# MBO.net
KiCad netlist of a schematic drawn in EAGLE
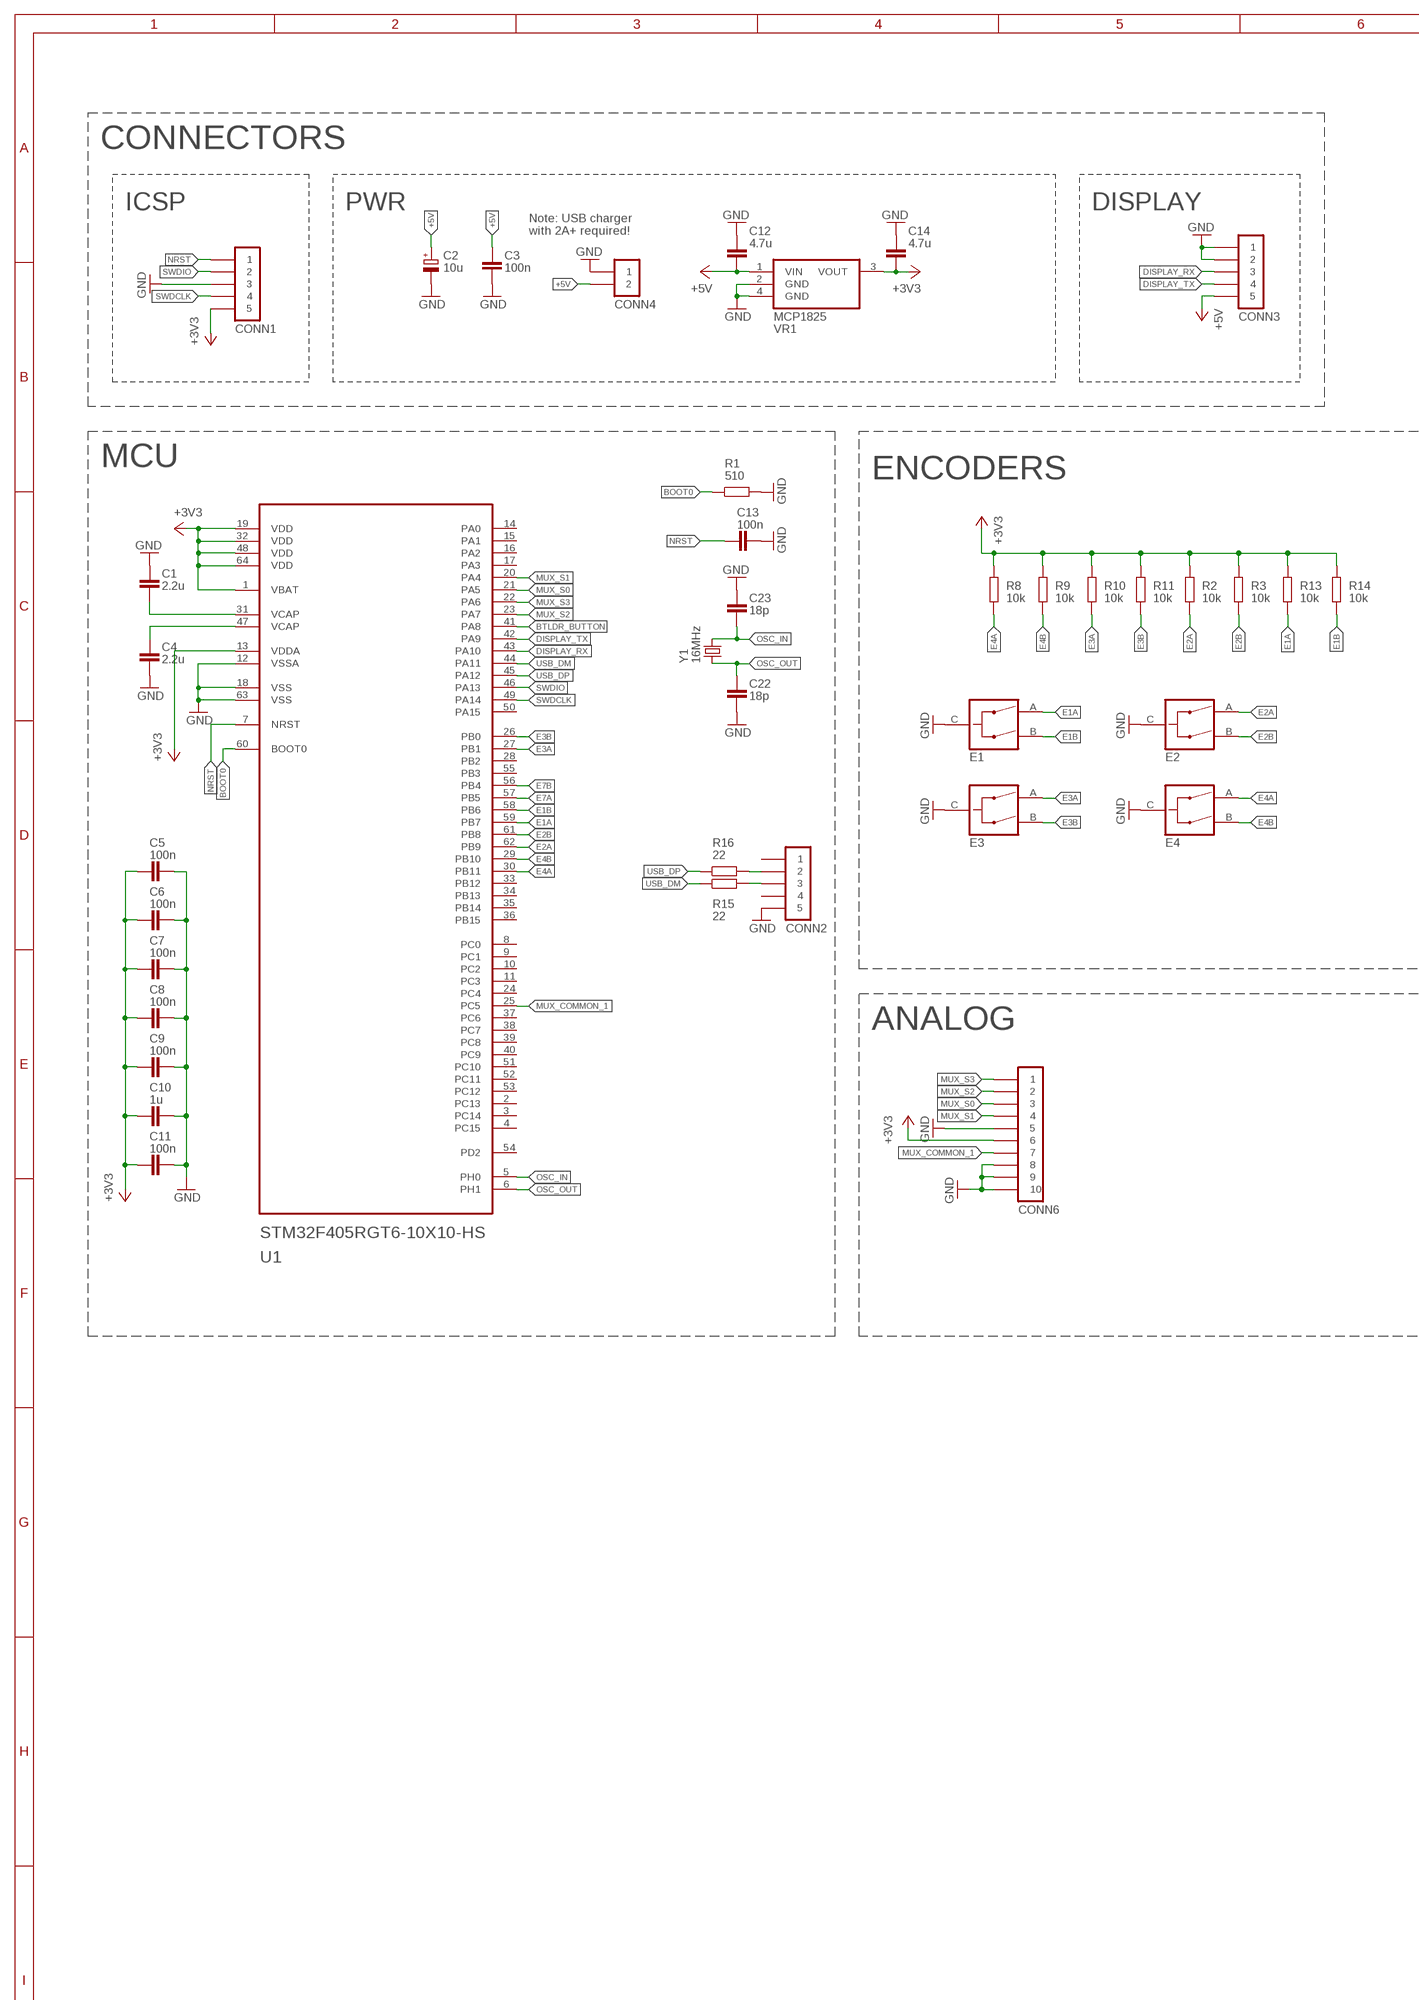
[diagram p0: schematic, sheet 1, part 1 of 2]
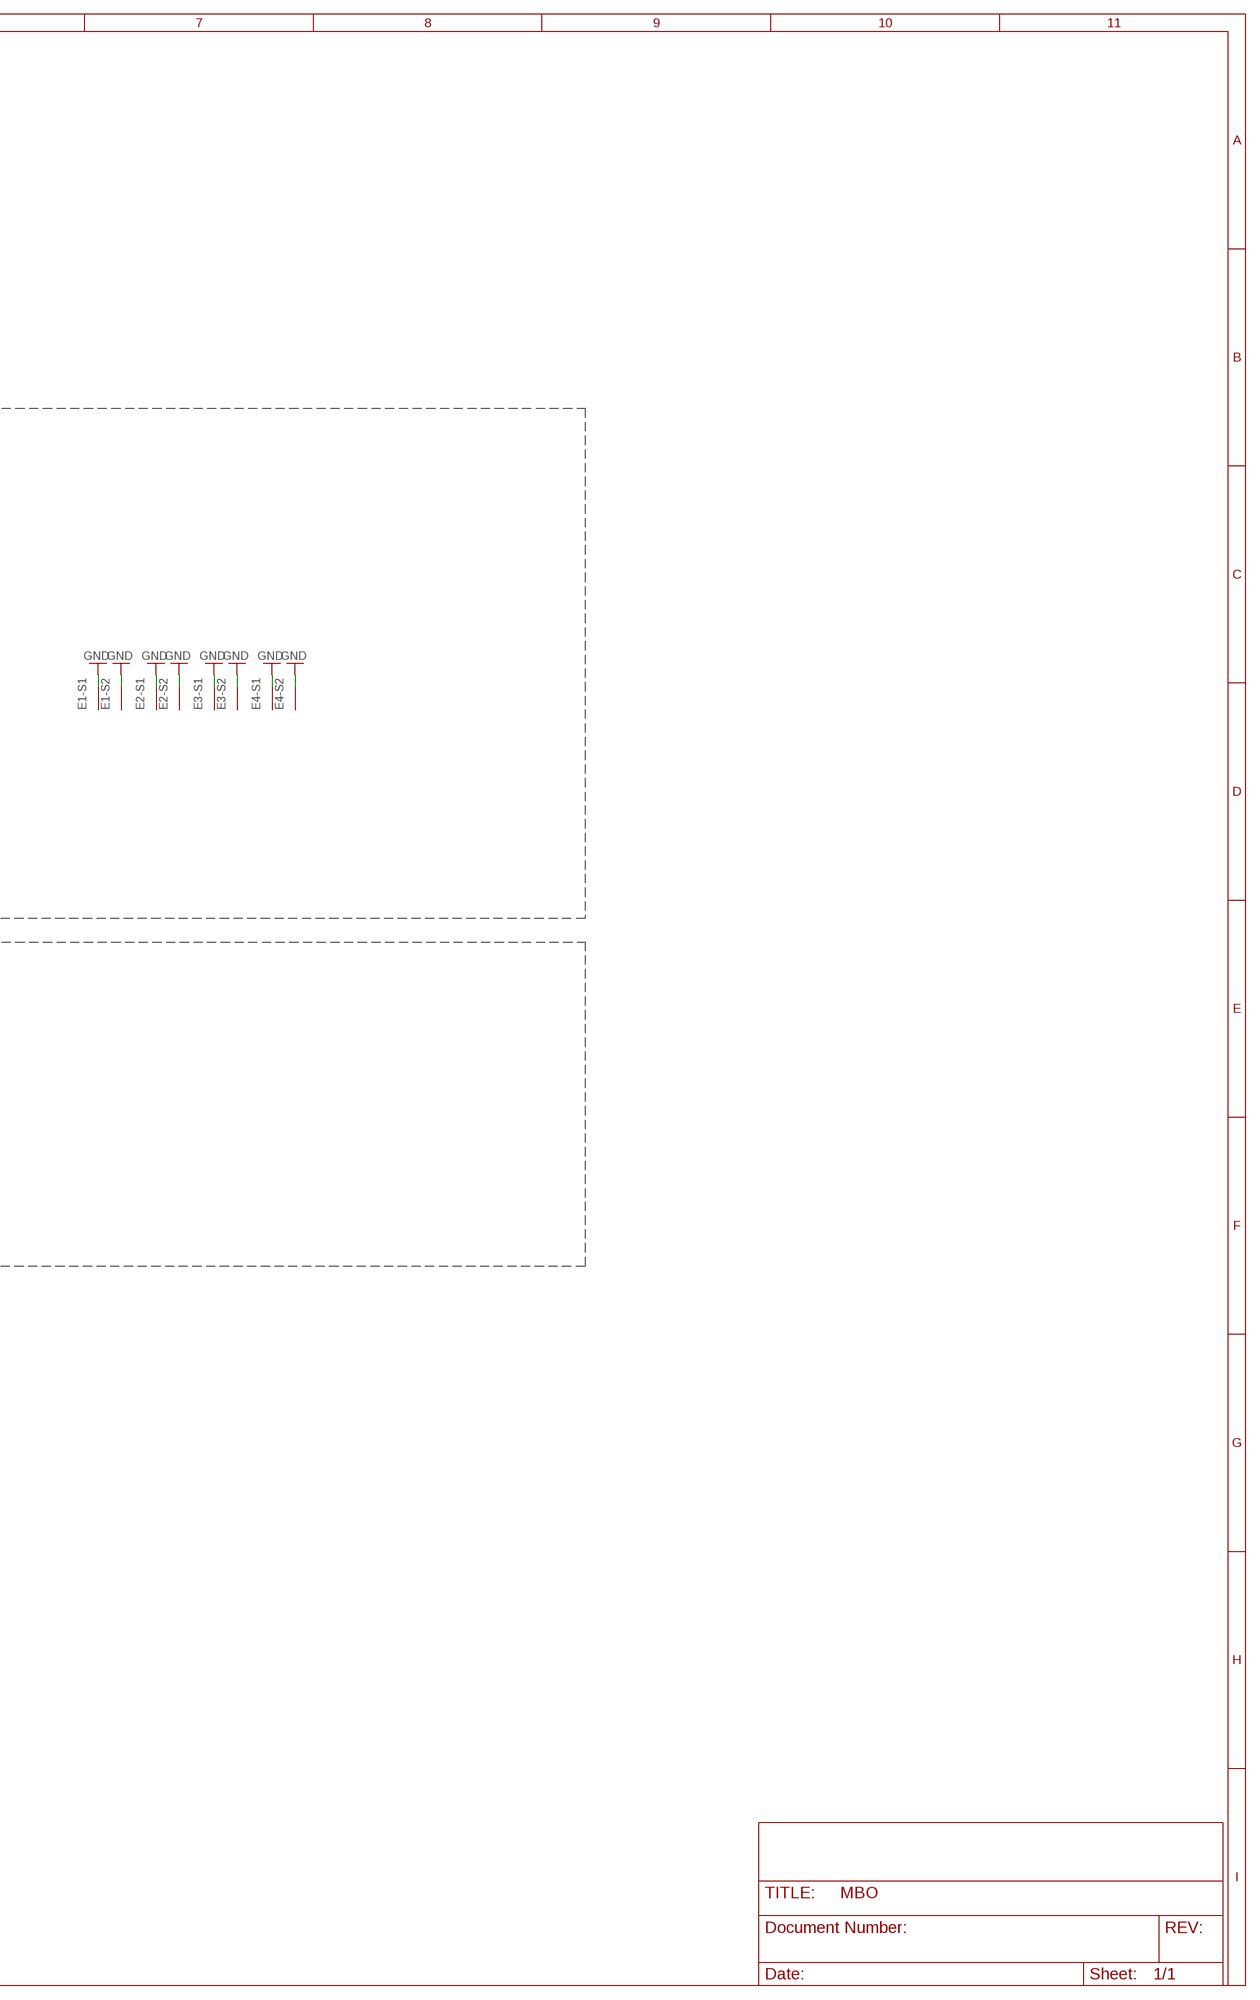
[diagram p1: schematic, sheet 1, part 2 of 2]

(export (version "E")
  (design (tool "Eeschema 10.0.6"))
  (components
    (comp (ref "C1")
      (value "2.2u")
      (footprint "eagle-import:C0805")
      (libsource (lib "eagle-import") (part "CAPACITOR-0805"))
    )
    (comp (ref "C2")
      (value "10u")
      (footprint "eagle-import:C-TH-E-0401")
      (libsource (lib "eagle-import") (part "ELECTROLYTIC_CAPACITOR-C-TH-E-0401"))
    )
    (comp (ref "C3")
      (value "100n")
      (footprint "eagle-import:C0805")
      (libsource (lib "eagle-import") (part "CAPACITOR-0805"))
    )
    (comp (ref "C4")
      (value "2.2u")
      (footprint "eagle-import:C0805")
      (libsource (lib "eagle-import") (part "CAPACITOR-0805"))
    )
    (comp (ref "C5")
      (value "100n")
      (footprint "eagle-import:C0805")
      (libsource (lib "eagle-import") (part "CAPACITOR-0805"))
    )
    (comp (ref "C6")
      (value "100n")
      (footprint "eagle-import:C0805")
      (libsource (lib "eagle-import") (part "CAPACITOR-0805"))
    )
    (comp (ref "C7")
      (value "100n")
      (footprint "eagle-import:C0805")
      (libsource (lib "eagle-import") (part "CAPACITOR-0805"))
    )
    (comp (ref "C8")
      (value "100n")
      (footprint "eagle-import:C0805")
      (libsource (lib "eagle-import") (part "CAPACITOR-0805"))
    )
    (comp (ref "C9")
      (value "100n")
      (footprint "eagle-import:C0805")
      (libsource (lib "eagle-import") (part "CAPACITOR-0805"))
    )
    (comp (ref "C10")
      (value "1u")
      (footprint "eagle-import:C0805")
      (libsource (lib "eagle-import") (part "CAPACITOR-0805"))
    )
    (comp (ref "C11")
      (value "100n")
      (footprint "eagle-import:C0805")
      (libsource (lib "eagle-import") (part "CAPACITOR-0805"))
    )
    (comp (ref "C12")
      (value "4.7u")
      (footprint "eagle-import:C0805")
      (libsource (lib "eagle-import") (part "CAPACITOR-0805"))
    )
    (comp (ref "C13")
      (value "100n")
      (footprint "eagle-import:C0805")
      (libsource (lib "eagle-import") (part "CAPACITOR-0805"))
    )
    (comp (ref "C14")
      (value "4.7u")
      (footprint "eagle-import:C0805")
      (libsource (lib "eagle-import") (part "CAPACITOR-0805"))
    )
    (comp (ref "C22")
      (value "18p")
      (footprint "eagle-import:C0805")
      (libsource (lib "eagle-import") (part "CAPACITOR-0805"))
    )
    (comp (ref "C23")
      (value "18p")
      (footprint "eagle-import:C0805")
      (libsource (lib "eagle-import") (part "CAPACITOR-0805"))
    )
    (comp (ref "CONN1")
      (value "PINHD-1X05-TH-2.54MM")
      (footprint "eagle-import:1X05-2.54")
      (libsource (lib "eagle-import") (part "PINHD-1X05-TH-2.54MM"))
    )
    (comp (ref "CONN2")
      (value "PINHD-1X05-JST-XH-H")
      (footprint "eagle-import:JST-XH-05P-H")
      (libsource (lib "eagle-import") (part "PINHD-1X05-JST-XH-H"))
    )
    (comp (ref "CONN3")
      (value "PINHD-1X05-JST-XH-H")
      (footprint "eagle-import:JST-XH-05P-H")
      (libsource (lib "eagle-import") (part "PINHD-1X05-JST-XH-H"))
    )
    (comp (ref "CONN4")
      (value "PINHD-1X02-JST-XH-H")
      (footprint "eagle-import:JST-XH-02P-H")
      (libsource (lib "eagle-import") (part "PINHD-1X02-JST-XH-H"))
    )
    (comp (ref "CONN6")
      (value "PINHD-1X10-FFC-1MM-Z")
      (footprint "eagle-import:MOLEX-52271-1079")
      (fields (field (name "MANUFACTURER") "Molex") (field (name "MPN") "52271-1079"))
      (libsource (lib "eagle-import") (part "PINHD-1X10-FFC-1MM-Z"))
    )
    (comp (ref "E1")
      (value "ALPS-EC12E24404AX")
      (footprint "eagle-import:EC12E-1")
      (libsource (lib "eagle-import") (part "ALPS-EC12E24404AX"))
    )
    (comp (ref "E2")
      (value "ALPS-EC12E24404AX")
      (footprint "eagle-import:EC12E-1")
      (libsource (lib "eagle-import") (part "ALPS-EC12E24404AX"))
    )
    (comp (ref "E3")
      (value "ALPS-EC12E24404AX")
      (footprint "eagle-import:EC12E-1")
      (libsource (lib "eagle-import") (part "ALPS-EC12E24404AX"))
    )
    (comp (ref "E4")
      (value "ALPS-EC12E24404AX")
      (footprint "eagle-import:EC12E-1")
      (libsource (lib "eagle-import") (part "ALPS-EC12E24404AX"))
    )
    (comp (ref "R1")
      (value "510")
      (footprint "eagle-import:R0805")
      (libsource (lib "eagle-import") (part "RESISTOR-0805"))
    )
    (comp (ref "R2")
      (value "10k")
      (footprint "eagle-import:R0805")
      (libsource (lib "eagle-import") (part "RESISTOR-0805"))
    )
    (comp (ref "R3")
      (value "10k")
      (footprint "eagle-import:R0805")
      (libsource (lib "eagle-import") (part "RESISTOR-0805"))
    )
    (comp (ref "R8")
      (value "10k")
      (footprint "eagle-import:R0805")
      (libsource (lib "eagle-import") (part "RESISTOR-0805"))
    )
    (comp (ref "R9")
      (value "10k")
      (footprint "eagle-import:R0805")
      (libsource (lib "eagle-import") (part "RESISTOR-0805"))
    )
    (comp (ref "R10")
      (value "10k")
      (footprint "eagle-import:R0805")
      (libsource (lib "eagle-import") (part "RESISTOR-0805"))
    )
    (comp (ref "R11")
      (value "10k")
      (footprint "eagle-import:R0805")
      (libsource (lib "eagle-import") (part "RESISTOR-0805"))
    )
    (comp (ref "R13")
      (value "10k")
      (footprint "eagle-import:R0805")
      (libsource (lib "eagle-import") (part "RESISTOR-0805"))
    )
    (comp (ref "R14")
      (value "10k")
      (footprint "eagle-import:R0805")
      (libsource (lib "eagle-import") (part "RESISTOR-0805"))
    )
    (comp (ref "R15")
      (value "22")
      (footprint "eagle-import:R0805")
      (libsource (lib "eagle-import") (part "RESISTOR-0805"))
    )
    (comp (ref "R16")
      (value "22")
      (footprint "eagle-import:R0805")
      (libsource (lib "eagle-import") (part "RESISTOR-0805"))
    )
    (comp (ref "U1")
      (value "STM32F405RGT6-10X10-HS")
      (footprint "eagle-import:TQFP-64-10X10-HS")
      (libsource (lib "eagle-import") (part "STM32F405RGT6-10X10-HS"))
    )
    (comp (ref "VR1")
      (value "MCP1825")
      (footprint "eagle-import:SOT223")
      (fields (field (name "MANUFACTURER") "Microchip") (field (name "MPN") "MCP1825S-3302E/DB"))
      (libsource (lib "eagle-import") (part "MCP1825"))
    )
    (comp (ref "Y1")
      (value "16MHz")
      (footprint "eagle-import:HC49US")
      (fields (field (name "MANUFACTURER") "TXC") (field (name "MPN") "9B-16.000MEEJ-B"))
      (libsource (lib "eagle-import") (part "CRYSTAL-HC49"))
    )
  )
  (nets
    (net (code "1") (name "+3V3") (class "Default")
      (node (ref "C10") (pin "1") (pinfunction "1_1") (pintype "passive"))
      (node (ref "C11") (pin "1") (pinfunction "1_1") (pintype "passive"))
      (node (ref "C14") (pin "1") (pinfunction "1_1") (pintype "passive"))
      (node (ref "C5") (pin "1") (pinfunction "1_1") (pintype "passive"))
      (node (ref "C6") (pin "1") (pinfunction "1_1") (pintype "passive"))
      (node (ref "C7") (pin "1") (pinfunction "1_1") (pintype "passive"))
      (node (ref "C8") (pin "1") (pinfunction "1_1") (pintype "passive"))
      (node (ref "C9") (pin "1") (pinfunction "1_1") (pintype "passive"))
      (node (ref "CONN1") (pin "5") (pinfunction "5_5") (pintype "passive"))
      (node (ref "CONN6") (pin "6") (pinfunction "6_6") (pintype "passive"))
      (node (ref "R10") (pin "2") (pinfunction "2_2") (pintype "passive"))
      (node (ref "R11") (pin "2") (pinfunction "2_2") (pintype "passive"))
      (node (ref "R13") (pin "2") (pinfunction "2_2") (pintype "passive"))
      (node (ref "R14") (pin "2") (pinfunction "2_2") (pintype "passive"))
      (node (ref "R2") (pin "2") (pinfunction "2_2") (pintype "passive"))
      (node (ref "R3") (pin "2") (pinfunction "2_2") (pintype "passive"))
      (node (ref "R8") (pin "2") (pinfunction "2_2") (pintype "passive"))
      (node (ref "R9") (pin "2") (pinfunction "2_2") (pintype "passive"))
      (node (ref "U1") (pin "1") (pinfunction "VBAT_1") (pintype "bidirectional"))
      (node (ref "U1") (pin "13") (pinfunction "VDDA_13") (pintype "bidirectional"))
      (node (ref "U1") (pin "19") (pinfunction "VDD_19") (pintype "bidirectional"))
      (node (ref "U1") (pin "32") (pinfunction "VDD_32") (pintype "bidirectional"))
      (node (ref "U1") (pin "48") (pinfunction "VDD_48") (pintype "bidirectional"))
      (node (ref "U1") (pin "64") (pinfunction "VDD_64") (pintype "bidirectional"))
      (node (ref "VR1") (pin "3") (pinfunction "VOUT_3") (pintype "passive"))
    )
    (net (code "2") (name "+5V") (class "Default")
      (node (ref "C12") (pin "1") (pinfunction "1_1") (pintype "passive"))
      (node (ref "C2") (pin "+") (pinfunction "+_+") (pintype "passive"))
      (node (ref "C3") (pin "1") (pinfunction "1_1") (pintype "passive"))
      (node (ref "CONN3") (pin "5") (pinfunction "5_5") (pintype "passive"))
      (node (ref "CONN4") (pin "2") (pinfunction "2_2") (pintype "passive"))
      (node (ref "VR1") (pin "1") (pinfunction "VIN_1") (pintype "passive"))
    )
    (net (code "3") (name "BOOT0") (class "Default")
      (node (ref "R1") (pin "1") (pinfunction "1_1") (pintype "passive"))
      (node (ref "U1") (pin "60") (pinfunction "BOOT0_60") (pintype "bidirectional"))
    )
    (net (code "4") (name "BTLDR_BUTTON") (class "Default")
      (node (ref "U1") (pin "41") (pinfunction "PA8_41") (pintype "bidirectional"))
    )
    (net (code "5") (name "DISPLAY_RX") (class "Default")
      (node (ref "CONN3") (pin "3") (pinfunction "3_3") (pintype "passive"))
      (node (ref "U1") (pin "43") (pinfunction "PA10_43") (pintype "bidirectional"))
    )
    (net (code "6") (name "DISPLAY_TX") (class "Default")
      (node (ref "CONN3") (pin "4") (pinfunction "4_4") (pintype "passive"))
      (node (ref "U1") (pin "42") (pinfunction "PA9_42") (pintype "bidirectional"))
    )
    (net (code "7") (name "E1A") (class "Default")
      (node (ref "E1") (pin "A") (pinfunction "A_A") (pintype "output"))
      (node (ref "R13") (pin "1") (pinfunction "1_1") (pintype "passive"))
      (node (ref "U1") (pin "59") (pinfunction "PB7_59") (pintype "bidirectional"))
    )
    (net (code "8") (name "E1B") (class "Default")
      (node (ref "E1") (pin "B") (pinfunction "B_B") (pintype "output"))
      (node (ref "R14") (pin "1") (pinfunction "1_1") (pintype "passive"))
      (node (ref "U1") (pin "58") (pinfunction "PB6_58") (pintype "bidirectional"))
    )
    (net (code "9") (name "E2A") (class "Default")
      (node (ref "E2") (pin "A") (pinfunction "A_A") (pintype "output"))
      (node (ref "R2") (pin "1") (pinfunction "1_1") (pintype "passive"))
      (node (ref "U1") (pin "62") (pinfunction "PB9_62") (pintype "bidirectional"))
    )
    (net (code "10") (name "E2B") (class "Default")
      (node (ref "E2") (pin "B") (pinfunction "B_B") (pintype "output"))
      (node (ref "R3") (pin "1") (pinfunction "1_1") (pintype "passive"))
      (node (ref "U1") (pin "61") (pinfunction "PB8_61") (pintype "bidirectional"))
    )
    (net (code "11") (name "E3A") (class "Default")
      (node (ref "E3") (pin "A") (pinfunction "A_A") (pintype "output"))
      (node (ref "R10") (pin "1") (pinfunction "1_1") (pintype "passive"))
      (node (ref "U1") (pin "27") (pinfunction "PB1_27") (pintype "bidirectional"))
    )
    (net (code "12") (name "E3B") (class "Default")
      (node (ref "E3") (pin "B") (pinfunction "B_B") (pintype "output"))
      (node (ref "R11") (pin "1") (pinfunction "1_1") (pintype "passive"))
      (node (ref "U1") (pin "26") (pinfunction "PB0_26") (pintype "bidirectional"))
    )
    (net (code "13") (name "E4A") (class "Default")
      (node (ref "E4") (pin "A") (pinfunction "A_A") (pintype "output"))
      (node (ref "R8") (pin "1") (pinfunction "1_1") (pintype "passive"))
      (node (ref "U1") (pin "30") (pinfunction "PB11_30") (pintype "bidirectional"))
    )
    (net (code "14") (name "E4B") (class "Default")
      (node (ref "E4") (pin "B") (pinfunction "B_B") (pintype "output"))
      (node (ref "R9") (pin "1") (pinfunction "1_1") (pintype "passive"))
      (node (ref "U1") (pin "29") (pinfunction "PB10_29") (pintype "bidirectional"))
    )
    (net (code "15") (name "E7A") (class "Default")
      (node (ref "U1") (pin "57") (pinfunction "PB5_57") (pintype "bidirectional"))
    )
    (net (code "16") (name "E7B") (class "Default")
      (node (ref "U1") (pin "56") (pinfunction "PB4_56") (pintype "bidirectional"))
    )
    (net (code "17") (name "GND") (class "Default")
      (node (ref "C1") (pin "1") (pinfunction "1_1") (pintype "passive"))
      (node (ref "C10") (pin "2") (pinfunction "2_2") (pintype "passive"))
      (node (ref "C11") (pin "2") (pinfunction "2_2") (pintype "passive"))
      (node (ref "C12") (pin "2") (pinfunction "2_2") (pintype "passive"))
      (node (ref "C13") (pin "2") (pinfunction "2_2") (pintype "passive"))
      (node (ref "C14") (pin "2") (pinfunction "2_2") (pintype "passive"))
      (node (ref "C2") (pin "-") (pinfunction "-_-") (pintype "passive"))
      (node (ref "C22") (pin "2") (pinfunction "2_2") (pintype "passive"))
      (node (ref "C23") (pin "1") (pinfunction "1_1") (pintype "passive"))
      (node (ref "C3") (pin "2") (pinfunction "2_2") (pintype "passive"))
      (node (ref "C4") (pin "2") (pinfunction "2_2") (pintype "passive"))
      (node (ref "C5") (pin "2") (pinfunction "2_2") (pintype "passive"))
      (node (ref "C6") (pin "2") (pinfunction "2_2") (pintype "passive"))
      (node (ref "C7") (pin "2") (pinfunction "2_2") (pintype "passive"))
      (node (ref "C8") (pin "2") (pinfunction "2_2") (pintype "passive"))
      (node (ref "C9") (pin "2") (pinfunction "2_2") (pintype "passive"))
      (node (ref "CONN1") (pin "3") (pinfunction "3_3") (pintype "passive"))
      (node (ref "CONN2") (pin "5") (pinfunction "5_5") (pintype "passive"))
      (node (ref "CONN3") (pin "1") (pinfunction "1_1") (pintype "passive"))
      (node (ref "CONN3") (pin "2") (pinfunction "2_2") (pintype "passive"))
      (node (ref "CONN4") (pin "1") (pinfunction "1_1") (pintype "passive"))
      (node (ref "CONN6") (pin "10") (pinfunction "10_10") (pintype "passive"))
      (node (ref "CONN6") (pin "5") (pinfunction "5_5") (pintype "passive"))
      (node (ref "CONN6") (pin "8") (pinfunction "8_8") (pintype "passive"))
      (node (ref "CONN6") (pin "9") (pinfunction "9_9") (pintype "passive"))
      (node (ref "E1") (pin "C") (pinfunction "C_C") (pintype "input"))
      (node (ref "E1") (pin "S1") (pinfunction "S_S1") (pintype "passive"))
      (node (ref "E1") (pin "S2") (pinfunction "S_S2") (pintype "passive"))
      (node (ref "E2") (pin "C") (pinfunction "C_C") (pintype "input"))
      (node (ref "E2") (pin "S1") (pinfunction "S_S1") (pintype "passive"))
      (node (ref "E2") (pin "S2") (pinfunction "S_S2") (pintype "passive"))
      (node (ref "E3") (pin "C") (pinfunction "C_C") (pintype "input"))
      (node (ref "E3") (pin "S1") (pinfunction "S_S1") (pintype "passive"))
      (node (ref "E3") (pin "S2") (pinfunction "S_S2") (pintype "passive"))
      (node (ref "E4") (pin "C") (pinfunction "C_C") (pintype "input"))
      (node (ref "E4") (pin "S1") (pinfunction "S_S1") (pintype "passive"))
      (node (ref "E4") (pin "S2") (pinfunction "S_S2") (pintype "passive"))
      (node (ref "R1") (pin "2") (pinfunction "2_2") (pintype "passive"))
      (node (ref "U1") (pin "12") (pinfunction "VSSA_12") (pintype "bidirectional"))
      (node (ref "U1") (pin "18") (pinfunction "VSS_18") (pintype "bidirectional"))
      (node (ref "U1") (pin "63") (pinfunction "VSS_63") (pintype "bidirectional"))
      (node (ref "VR1") (pin "2") (pinfunction "GND_2") (pintype "passive"))
      (node (ref "VR1") (pin "4") (pinfunction "GND_4") (pintype "passive"))
    )
    (net (code "18") (name "MUX_COMMON_1") (class "Default")
      (node (ref "CONN6") (pin "7") (pinfunction "7_7") (pintype "passive"))
      (node (ref "U1") (pin "25") (pinfunction "PC5_25") (pintype "bidirectional"))
    )
    (net (code "19") (name "MUX_S0") (class "Default")
      (node (ref "CONN6") (pin "3") (pinfunction "3_3") (pintype "passive"))
      (node (ref "U1") (pin "21") (pinfunction "PA5_21") (pintype "bidirectional"))
    )
    (net (code "20") (name "MUX_S1") (class "Default")
      (node (ref "CONN6") (pin "4") (pinfunction "4_4") (pintype "passive"))
      (node (ref "U1") (pin "20") (pinfunction "PA4_20") (pintype "bidirectional"))
    )
    (net (code "21") (name "MUX_S2") (class "Default")
      (node (ref "CONN6") (pin "2") (pinfunction "2_2") (pintype "passive"))
      (node (ref "U1") (pin "23") (pinfunction "PA7_23") (pintype "bidirectional"))
    )
    (net (code "22") (name "MUX_S3") (class "Default")
      (node (ref "CONN6") (pin "1") (pinfunction "1_1") (pintype "passive"))
      (node (ref "U1") (pin "22") (pinfunction "PA6_22") (pintype "bidirectional"))
    )
    (net (code "23") (name "NRST") (class "Default")
      (node (ref "C13") (pin "1") (pinfunction "1_1") (pintype "passive"))
      (node (ref "CONN1") (pin "1") (pinfunction "1_1") (pintype "passive"))
      (node (ref "U1") (pin "7") (pinfunction "NRST_7") (pintype "bidirectional"))
    )
    (net (code "24") (name "Net-(C1-Pad2)") (class "Default")
      (node (ref "C1") (pin "2") (pinfunction "2_2") (pintype "passive"))
      (node (ref "U1") (pin "31") (pinfunction "VCAP_31") (pintype "bidirectional"))
    )
    (net (code "25") (name "Net-(C4-Pad1)") (class "Default")
      (node (ref "C4") (pin "1") (pinfunction "1_1") (pintype "passive"))
      (node (ref "U1") (pin "47") (pinfunction "VCAP_47") (pintype "bidirectional"))
    )
    (net (code "26") (name "Net-(CONN2-Pad2)") (class "Default")
      (node (ref "CONN2") (pin "2") (pinfunction "2_2") (pintype "passive"))
      (node (ref "R16") (pin "2") (pinfunction "2_2") (pintype "passive"))
    )
    (net (code "27") (name "Net-(CONN2-Pad3)") (class "Default")
      (node (ref "CONN2") (pin "3") (pinfunction "3_3") (pintype "passive"))
      (node (ref "R15") (pin "2") (pinfunction "2_2") (pintype "passive"))
    )
    (net (code "28") (name "OSC_IN") (class "Default")
      (node (ref "C23") (pin "2") (pinfunction "2_2") (pintype "passive"))
      (node (ref "U1") (pin "5") (pinfunction "PH0_5") (pintype "bidirectional"))
      (node (ref "Y1") (pin "2") (pinfunction "2_2") (pintype "passive"))
    )
    (net (code "29") (name "OSC_OUT") (class "Default")
      (node (ref "C22") (pin "1") (pinfunction "1_1") (pintype "passive"))
      (node (ref "U1") (pin "6") (pinfunction "PH1_6") (pintype "bidirectional"))
      (node (ref "Y1") (pin "1") (pinfunction "1_1") (pintype "passive"))
    )
    (net (code "30") (name "SWDCLK") (class "Default")
      (node (ref "CONN1") (pin "4") (pinfunction "4_4") (pintype "passive"))
      (node (ref "U1") (pin "49") (pinfunction "PA14_49") (pintype "bidirectional"))
    )
    (net (code "31") (name "SWDIO") (class "Default")
      (node (ref "CONN1") (pin "2") (pinfunction "2_2") (pintype "passive"))
      (node (ref "U1") (pin "46") (pinfunction "PA13_46") (pintype "bidirectional"))
    )
    (net (code "32") (name "USB_DM") (class "Default")
      (node (ref "R15") (pin "1") (pinfunction "1_1") (pintype "passive"))
      (node (ref "U1") (pin "44") (pinfunction "PA11_44") (pintype "bidirectional"))
    )
    (net (code "33") (name "USB_DP") (class "Default")
      (node (ref "R16") (pin "1") (pinfunction "1_1") (pintype "passive"))
      (node (ref "U1") (pin "45") (pinfunction "PA12_45") (pintype "bidirectional"))
    )
    (net (code "34") (name "unconnected-(CONN2-Pad1)") (class "Default")
      (node (ref "CONN2") (pin "1") (pinfunction "1_1") (pintype "passive"))
    )
    (net (code "35") (name "unconnected-(CONN2-Pad4)") (class "Default")
      (node (ref "CONN2") (pin "4") (pinfunction "4_4") (pintype "passive"))
    )
    (net (code "36") (name "unconnected-(U1-PA0-Pad14)") (class "Default")
      (node (ref "U1") (pin "14") (pinfunction "PA0_14") (pintype "bidirectional"))
    )
    (net (code "37") (name "unconnected-(U1-PA1-Pad15)") (class "Default")
      (node (ref "U1") (pin "15") (pinfunction "PA1_15") (pintype "bidirectional"))
    )
    (net (code "38") (name "unconnected-(U1-PA2-Pad16)") (class "Default")
      (node (ref "U1") (pin "16") (pinfunction "PA2_16") (pintype "bidirectional"))
    )
    (net (code "39") (name "unconnected-(U1-PA3-Pad17)") (class "Default")
      (node (ref "U1") (pin "17") (pinfunction "PA3_17") (pintype "bidirectional"))
    )
    (net (code "40") (name "unconnected-(U1-PA15-Pad50)") (class "Default")
      (node (ref "U1") (pin "50") (pinfunction "PA15_50") (pintype "bidirectional"))
    )
    (net (code "41") (name "unconnected-(U1-PB2-Pad28)") (class "Default")
      (node (ref "U1") (pin "28") (pinfunction "PB2_28") (pintype "bidirectional"))
    )
    (net (code "42") (name "unconnected-(U1-PB3-Pad55)") (class "Default")
      (node (ref "U1") (pin "55") (pinfunction "PB3_55") (pintype "bidirectional"))
    )
    (net (code "43") (name "unconnected-(U1-PB12-Pad33)") (class "Default")
      (node (ref "U1") (pin "33") (pinfunction "PB12_33") (pintype "bidirectional"))
    )
    (net (code "44") (name "unconnected-(U1-PB13-Pad34)") (class "Default")
      (node (ref "U1") (pin "34") (pinfunction "PB13_34") (pintype "bidirectional"))
    )
    (net (code "45") (name "unconnected-(U1-PB14-Pad35)") (class "Default")
      (node (ref "U1") (pin "35") (pinfunction "PB14_35") (pintype "bidirectional"))
    )
    (net (code "46") (name "unconnected-(U1-PB15-Pad36)") (class "Default")
      (node (ref "U1") (pin "36") (pinfunction "PB15_36") (pintype "bidirectional"))
    )
    (net (code "47") (name "unconnected-(U1-PC0-Pad8)") (class "Default")
      (node (ref "U1") (pin "8") (pinfunction "PC0_8") (pintype "bidirectional"))
    )
    (net (code "48") (name "unconnected-(U1-PC1-Pad9)") (class "Default")
      (node (ref "U1") (pin "9") (pinfunction "PC1_9") (pintype "bidirectional"))
    )
    (net (code "49") (name "unconnected-(U1-PC2-Pad10)") (class "Default")
      (node (ref "U1") (pin "10") (pinfunction "PC2_10") (pintype "bidirectional"))
    )
    (net (code "50") (name "unconnected-(U1-PC3-Pad11)") (class "Default")
      (node (ref "U1") (pin "11") (pinfunction "PC3_11") (pintype "bidirectional"))
    )
    (net (code "51") (name "unconnected-(U1-PC4-Pad24)") (class "Default")
      (node (ref "U1") (pin "24") (pinfunction "PC4_24") (pintype "bidirectional"))
    )
    (net (code "52") (name "unconnected-(U1-PC6-Pad37)") (class "Default")
      (node (ref "U1") (pin "37") (pinfunction "PC6_37") (pintype "bidirectional"))
    )
    (net (code "53") (name "unconnected-(U1-PC7-Pad38)") (class "Default")
      (node (ref "U1") (pin "38") (pinfunction "PC7_38") (pintype "bidirectional"))
    )
    (net (code "54") (name "unconnected-(U1-PC8-Pad39)") (class "Default")
      (node (ref "U1") (pin "39") (pinfunction "PC8_39") (pintype "bidirectional"))
    )
    (net (code "55") (name "unconnected-(U1-PC9-Pad40)") (class "Default")
      (node (ref "U1") (pin "40") (pinfunction "PC9_40") (pintype "bidirectional"))
    )
    (net (code "56") (name "unconnected-(U1-PC10-Pad51)") (class "Default")
      (node (ref "U1") (pin "51") (pinfunction "PC10_51") (pintype "bidirectional"))
    )
    (net (code "57") (name "unconnected-(U1-PC11-Pad52)") (class "Default")
      (node (ref "U1") (pin "52") (pinfunction "PC11_52") (pintype "bidirectional"))
    )
    (net (code "58") (name "unconnected-(U1-PC12-Pad53)") (class "Default")
      (node (ref "U1") (pin "53") (pinfunction "PC12_53") (pintype "bidirectional"))
    )
    (net (code "59") (name "unconnected-(U1-PC13-Pad2)") (class "Default")
      (node (ref "U1") (pin "2") (pinfunction "PC13_2") (pintype "bidirectional"))
    )
    (net (code "60") (name "unconnected-(U1-PC14-Pad3)") (class "Default")
      (node (ref "U1") (pin "3") (pinfunction "PC14_3") (pintype "bidirectional"))
    )
    (net (code "61") (name "unconnected-(U1-PC15-Pad4)") (class "Default")
      (node (ref "U1") (pin "4") (pinfunction "PC15_4") (pintype "bidirectional"))
    )
    (net (code "62") (name "unconnected-(U1-PD2-Pad54)") (class "Default")
      (node (ref "U1") (pin "54") (pinfunction "PD2_54") (pintype "bidirectional"))
    )
  )
)
